# SH6_-_BROADCOM_ENCODER.net
KiCad netlist of a schematic drawn in Altium Designer
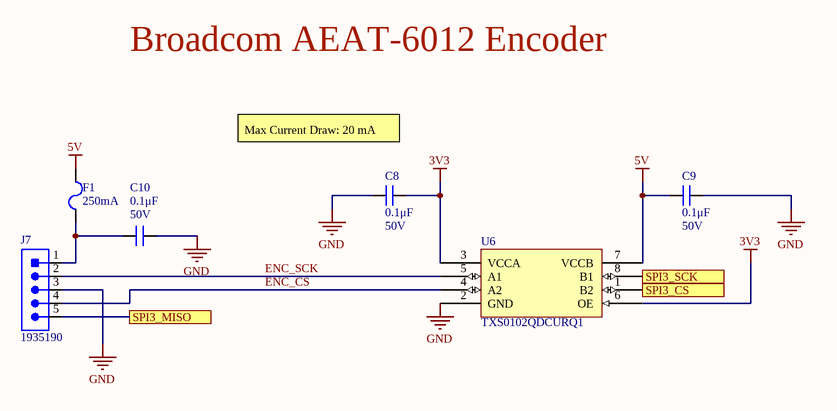
[diagram p0: SH6 - BROADCOM ENCODER.SchDoc]

(export (version "E")
  (design (tool "Eeschema 10.0.6"))
  (components
    (comp (ref "C8")
      (value "0.1μF")
      (footprint "CAP2012")
      (description "CAP CER 0.1UF 50V X7R 0805")
      (fields
        (field (name "LCSC PART #") "C49678")
        (field (name "VOLTAGE RATING") "50V")
        (field (name "Comment") "CAP_0.1uF_50V_0805")
      )
      (libsource (lib "UWRT_Schematic_Library_2020") (part "CAP_0.1uF_50V_0805"))
    )
    (comp (ref "C9")
      (value "0.1μF")
      (footprint "CAP2012")
      (description "CAP CER 0.1UF 50V X7R 0805")
      (fields
        (field (name "LCSC PART #") "C49678")
        (field (name "VOLTAGE RATING") "50V")
        (field (name "Comment") "CAP_0.1uF_50V_0805")
      )
      (libsource (lib "UWRT_Schematic_Library_2020") (part "CAP_0.1uF_50V_0805"))
    )
    (comp (ref "C10")
      (value "0.1μF")
      (footprint "CAP2012")
      (description "CAP CER 0.1UF 50V X7R 0805")
      (fields
        (field (name "VOLTAGE RATING") "50V")
        (field (name "LCSC PART #") "C49678")
        (field (name "Comment") "CAP_0.1uF_50V_0805")
      )
      (libsource (lib "UWRT_Schematic_Library_2020") (part "CAP_0.1uF_50V_0805"))
    )
    (comp (ref "F1")
      (value "FUSE_250mA_1206")
      (footprint "FUSE_1206")
      (description "FUSE BOARD MNT 250MA 125VAC/VDC")
      (fields (field (name "CURRENT RATING") "250mA"))
      (libsource (lib "UWRT_Schematic_Library_2020") (part "FUSE_250mA_1206"))
    )
    (comp (ref "J7")
      (value "CON_5POS_SCREW_TERM")
      (footprint "1935190")
      (description "TERM BLK 5POS SIDE ENTRY 5MM")
      (fields (field (name "MANUFACTURER PART NUMBER 1") "1935190"))
      (libsource (lib "UWRT_Schematic_Library_2020") (part "CON_5POS_SCREW_TERM"))
    )
    (comp (ref "U6")
      (value "IC_LVL_SHIFTER_2_CH")
      (footprint "TXS0102QDCURQ1")
      (description "IC TRNSLTR BIDIRECTIONAL US8")
      (fields (field (name "MANUFACTURER PART NUMBER 1") "TXS0102QDCURQ1"))
      (libsource (lib "UWRT_Schematic_Library_2020") (part "IC_LVL_SHIFTER_2_CH"))
    )
  )
  (nets
    (net (code "1") (name "/ENC_CS") (class "Default")
      (node (ref "J7") (pin "4") (pinfunction "4_4") (pintype "passive"))
      (node (ref "U6") (pin "4") (pinfunction "A2_4") (pintype "bidirectional"))
    )
    (net (code "2") (name "/ENC_SCK") (class "Default")
      (node (ref "J7") (pin "2") (pinfunction "2_2") (pintype "passive"))
      (node (ref "U6") (pin "5") (pinfunction "A1_5") (pintype "bidirectional"))
    )
    (net (code "3") (name "/SPI3_CS") (class "Default")
      (node (ref "U6") (pin "1") (pinfunction "B2_1") (pintype "bidirectional"))
    )
    (net (code "4") (name "/SPI3_MISO") (class "Default")
      (node (ref "J7") (pin "5") (pinfunction "5_5") (pintype "passive"))
    )
    (net (code "5") (name "/SPI3_SCK") (class "Default")
      (node (ref "U6") (pin "8") (pinfunction "B1_8") (pintype "bidirectional"))
    )
    (net (code "6") (name "3V3") (class "Default")
      (node (ref "C8") (pin "2") (pinfunction "2_2") (pintype "passive"))
      (node (ref "U6") (pin "3") (pinfunction "VCCA_3") (pintype "power_in"))
      (node (ref "U6") (pin "6") (pinfunction "OE_6") (pintype "input"))
    )
    (net (code "7") (name "5V") (class "Default")
      (node (ref "C9") (pin "1") (pinfunction "1_1") (pintype "passive"))
      (node (ref "F1") (pin "1") (pinfunction "1_1") (pintype "passive"))
      (node (ref "U6") (pin "7") (pinfunction "VCCB_7") (pintype "power_in"))
    )
    (net (code "8") (name "GND") (class "Default")
      (node (ref "C10") (pin "1") (pinfunction "1_1") (pintype "passive"))
      (node (ref "C8") (pin "1") (pinfunction "1_1") (pintype "passive"))
      (node (ref "C9") (pin "2") (pinfunction "2_2") (pintype "passive"))
      (node (ref "J7") (pin "3") (pinfunction "3_3") (pintype "passive"))
      (node (ref "U6") (pin "2") (pinfunction "GND_2") (pintype "power_in"))
    )
    (net (code "9") (name "Net-(C10-Pad2)") (class "Default")
      (node (ref "C10") (pin "2") (pinfunction "2_2") (pintype "passive"))
      (node (ref "F1") (pin "2") (pinfunction "2_2") (pintype "passive"))
      (node (ref "J7") (pin "1") (pinfunction "1_1") (pintype "passive"))
    )
  )
)
